# Sheet4.net
KiCad netlist of a schematic drawn in Altium Designer
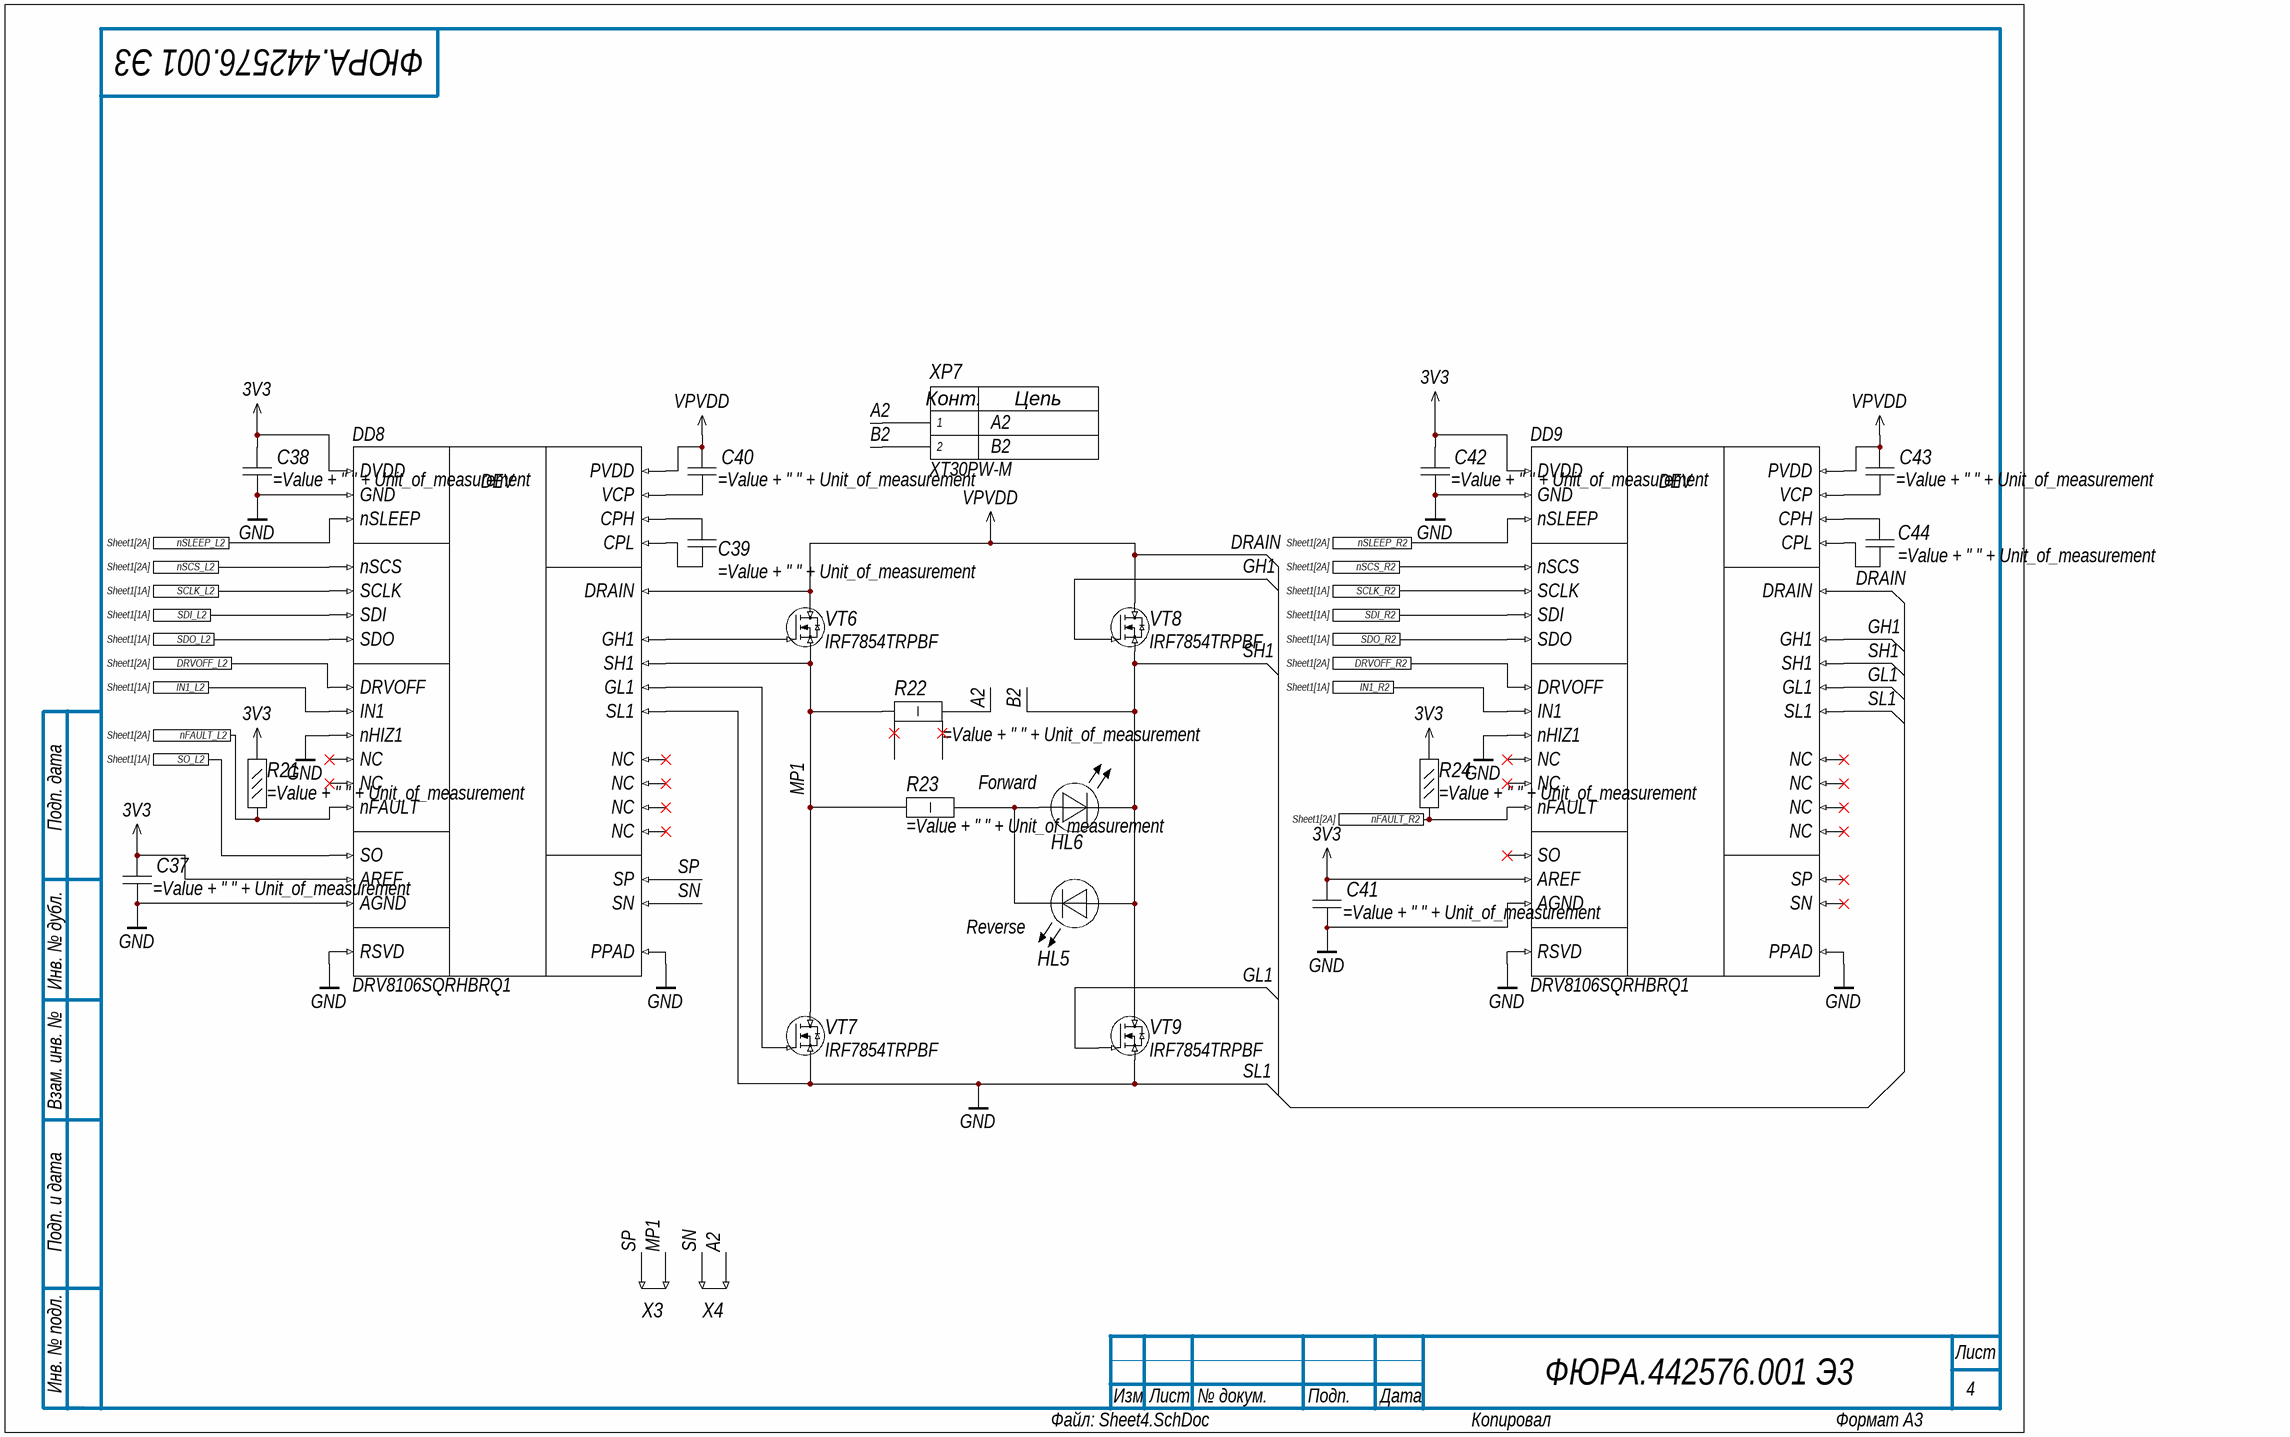
[diagram p0: Sheet4.SchDoc]

(export (version "E")
  (design (tool "Eeschema 10.0.6"))
  (components
    (comp (ref "C37")
      (value "1мкФ 6.3В")
      (footprint "CAP_0603")
      (description "Конденсатор керамический, типоразмера 0603")
      (libsource (lib "SimpleComponents") (part "CAP_0603"))
    )
    (comp (ref "C38")
      (value "1мкФ 6.3В")
      (footprint "CAP_0603")
      (description "Конденсатор керамический, типоразмера 0603")
      (libsource (lib "SimpleComponents") (part "CAP_0603"))
    )
    (comp (ref "C39")
      (value "0,1мкФ 50 В")
      (footprint "CAP_0603")
      (description "Конденсатор керамический, типоразмера 0603")
      (libsource (lib "SimpleComponents") (part "CAP_0603"))
    )
    (comp (ref "C40")
      (value "1мкФ 16 В")
      (footprint "CAP_0603")
      (description "Конденсатор керамический, типоразмера 0603")
      (libsource (lib "SimpleComponents") (part "CAP_0603"))
    )
    (comp (ref "C41")
      (value "1мкФ 6.3В")
      (footprint "CAP_0603")
      (description "Конденсатор керамический, типоразмера 0603")
      (libsource (lib "SimpleComponents") (part "CAP_0603"))
    )
    (comp (ref "C42")
      (value "1мкФ 6.3В")
      (footprint "CAP_0603")
      (description "Конденсатор керамический, типоразмера 0603")
      (libsource (lib "SimpleComponents") (part "CAP_0603"))
    )
    (comp (ref "C43")
      (value "1мкФ 16 В")
      (footprint "CAP_0603")
      (description "Конденсатор керамический, типоразмера 0603")
      (libsource (lib "SimpleComponents") (part "CAP_0603"))
    )
    (comp (ref "C44")
      (value "0,1мкФ 50 В")
      (footprint "CAP_0603")
      (description "Конденсатор керамический, типоразмера 0603")
      (libsource (lib "SimpleComponents") (part "CAP_0603"))
    )
    (comp (ref "DD8")
      (value "DRV8106SQRHBRQ1")
      (footprint "VQFN32")
      (libsource (lib "ICs") (part "DRV8106SQRHBRQ1"))
    )
    (comp (ref "DD9")
      (value "DRV8106SQRHBRQ1")
      (footprint "VQFN32")
      (libsource (lib "ICs") (part "DRV8106SQRHBRQ1"))
    )
    (comp (ref "HL5") (value "3") (footprint "LED_0805") (libsource (lib "Complicated") (part "LED_0805")))
    (comp (ref "HL6") (value "3") (footprint "LED_0805") (libsource (lib "Complicated") (part "LED_0805")))
    (comp (ref "R21")
      (value "10кОм")
      (footprint "RES_0603")
      (description "Резистор, типоразмера 0603")
      (libsource (lib "SimpleComponents") (part "RES_0603"))
    )
    (comp (ref "R22")
      (value "7.5мОм")
      (footprint "RES_2512")
      (description "Резистор, типоразмера 2512")
      (libsource (lib "SimpleComponents") (part "ResShunt_2512"))
    )
    (comp (ref "R23")
      (value "1.8кОм")
      (footprint "RES_2512")
      (description "Резистор, типоразмера 2512")
      (libsource (lib "SimpleComponents") (part "RES_2512"))
    )
    (comp (ref "R24")
      (value "10кОм")
      (footprint "RES_0603")
      (description "Резистор, типоразмера 0603")
      (libsource (lib "SimpleComponents") (part "RES_0603"))
    )
    (comp (ref "VT6")
      (value "IRF7854TRPBF")
      (footprint "SOP-8 WithoutTP")
      (description "Транзистор, HEXFET, N-канал, 80В, 10А [SOIC-8]")
      (libsource (lib "Complicated") (part "IRF7854TRPBF"))
    )
    (comp (ref "VT7")
      (value "IRF7854TRPBF")
      (footprint "SOP-8 WithoutTP")
      (description "Транзистор, HEXFET, N-канал, 80В, 10А [SOIC-8]")
      (libsource (lib "Complicated") (part "IRF7854TRPBF"))
    )
    (comp (ref "VT8")
      (value "IRF7854TRPBF")
      (footprint "SOP-8 WithoutTP")
      (description "Транзистор, HEXFET, N-канал, 80В, 10А [SOIC-8]")
      (libsource (lib "Complicated") (part "IRF7854TRPBF"))
    )
    (comp (ref "VT9")
      (value "IRF7854TRPBF")
      (footprint "SOP-8 WithoutTP")
      (description "Транзистор, HEXFET, N-канал, 80В, 10А [SOIC-8]")
      (libsource (lib "Complicated") (part "IRF7854TRPBF"))
    )
    (comp (ref "X3")
      (value "Обозначение при заказе")
      (footprint "NetTie")
      (description "Описание свойств компонента")
      (libsource (lib "SimpleComponents") (part "NetTie"))
    )
    (comp (ref "X4")
      (value "Обозначение при заказе")
      (footprint "NetTie")
      (description "Описание свойств компонента")
      (libsource (lib "SimpleComponents") (part "NetTie"))
    )
    (comp (ref "XP7")
      (value "XT30PW-M")
      (footprint "XT30PW-M")
      (description "Socket; DC supply; XT30; male; PIN: 2; on PCBs; THT; yellow; 15A; 500V")
      (libsource (lib "SimpleComponents") (part "XT30PW-M"))
    )
  )
  (nets
    (net (code "1") (name "/A2") (class "Default")
      (node (ref "R22") (pin "1") (pinfunction "1_1") (pintype "passive"))
      (node (ref "X4") (pin "2") (pinfunction "2_2") (pintype "input"))
      (node (ref "XP7") (pin "1") (pinfunction "1_1") (pintype "passive"))
    )
    (net (code "2") (name "/B2") (class "Default")
      (node (ref "DD9") (pin "21") (pinfunction "SH1_21") (pintype "input"))
      (node (ref "HL5") (pin "A") (pinfunction "2_A") (pintype "passive"))
      (node (ref "HL6") (pin "C") (pinfunction "1_C") (pintype "passive"))
      (node (ref "VT8") (pin "2") (pinfunction "2_2") (pintype "input"))
      (node (ref "VT9") (pin "3") (pinfunction "3_3") (pintype "input"))
      (node (ref "XP7") (pin "2") (pinfunction "2_2") (pintype "passive"))
    )
    (net (code "3") (name "/DRVOFF_L2") (class "Default")
      (node (ref "DD8") (pin "12") (pinfunction "DRVOFF_12") (pintype "input"))
    )
    (net (code "4") (name "/DRVOFF_R2") (class "Default")
      (node (ref "DD9") (pin "12") (pinfunction "DRVOFF_12") (pintype "input"))
    )
    (net (code "5") (name "/GH1") (class "Default")
      (node (ref "DD9") (pin "20") (pinfunction "GH1_20") (pintype "input"))
      (node (ref "VT8") (pin "1") (pinfunction "1_1") (pintype "input"))
    )
    (net (code "6") (name "/GL1") (class "Default")
      (node (ref "DD9") (pin "22") (pinfunction "GL1_22") (pintype "input"))
      (node (ref "VT9") (pin "1") (pinfunction "1_1") (pintype "input"))
    )
    (net (code "7") (name "/IN1_L2") (class "Default")
      (node (ref "DD8") (pin "7") (pinfunction "IN1_7") (pintype "input"))
    )
    (net (code "8") (name "/IN1_R2") (class "Default")
      (node (ref "DD9") (pin "7") (pinfunction "IN1_7") (pintype "input"))
    )
    (net (code "9") (name "/MP1") (class "Default")
      (node (ref "DD8") (pin "21") (pinfunction "SH1_21") (pintype "input"))
      (node (ref "R22") (pin "2") (pinfunction "2_2") (pintype "passive"))
      (node (ref "R23") (pin "1") (pinfunction "1_1") (pintype "passive"))
      (node (ref "VT6") (pin "2") (pinfunction "2_2") (pintype "input"))
      (node (ref "VT7") (pin "3") (pinfunction "3_3") (pintype "input"))
      (node (ref "X3") (pin "2") (pinfunction "2_2") (pintype "input"))
    )
    (net (code "10") (name "/SCLK_L2") (class "Default")
      (node (ref "DD8") (pin "4") (pinfunction "SCLK_4") (pintype "input"))
    )
    (net (code "11") (name "/SCLK_R2") (class "Default")
      (node (ref "DD9") (pin "4") (pinfunction "SCLK_4") (pintype "input"))
    )
    (net (code "12") (name "/SDI_L2") (class "Default")
      (node (ref "DD8") (pin "5") (pinfunction "SDI_5") (pintype "input"))
    )
    (net (code "13") (name "/SDI_R2") (class "Default")
      (node (ref "DD9") (pin "5") (pinfunction "SDI_5") (pintype "input"))
    )
    (net (code "14") (name "/SDO_L2") (class "Default")
      (node (ref "DD8") (pin "6") (pinfunction "SDO_6") (pintype "input"))
    )
    (net (code "15") (name "/SDO_R2") (class "Default")
      (node (ref "DD9") (pin "6") (pinfunction "SDO_6") (pintype "input"))
    )
    (net (code "16") (name "/SN") (class "Default")
      (node (ref "DD8") (pin "19") (pinfunction "SN_19") (pintype "input"))
      (node (ref "X4") (pin "1") (pinfunction "1_1") (pintype "input"))
    )
    (net (code "17") (name "/SO_L2") (class "Default")
      (node (ref "DD8") (pin "14") (pinfunction "SO_14") (pintype "input"))
    )
    (net (code "18") (name "/SP") (class "Default")
      (node (ref "DD8") (pin "18") (pinfunction "SP_18") (pintype "input"))
      (node (ref "X3") (pin "1") (pinfunction "1_1") (pintype "input"))
    )
    (net (code "19") (name "/nFAULT_L2") (class "Default")
      (node (ref "DD8") (pin "13") (pinfunction "nFAULT_13") (pintype "input"))
      (node (ref "R21") (pin "1") (pinfunction "1_1") (pintype "passive"))
    )
    (net (code "20") (name "/nFAULT_R2") (class "Default")
      (node (ref "DD9") (pin "13") (pinfunction "nFAULT_13") (pintype "input"))
      (node (ref "R24") (pin "1") (pinfunction "1_1") (pintype "passive"))
    )
    (net (code "21") (name "/nSCS_L2") (class "Default")
      (node (ref "DD8") (pin "3") (pinfunction "nSCS_3") (pintype "input"))
    )
    (net (code "22") (name "/nSCS_R2") (class "Default")
      (node (ref "DD9") (pin "3") (pinfunction "nSCS_3") (pintype "input"))
    )
    (net (code "23") (name "/nSLEEP_L2") (class "Default")
      (node (ref "DD8") (pin "11") (pinfunction "nSLEEP_11") (pintype "input"))
    )
    (net (code "24") (name "/nSLEEP_R2") (class "Default")
      (node (ref "DD9") (pin "11") (pinfunction "nSLEEP_11") (pintype "input"))
    )
    (net (code "25") (name "3V3") (class "Default")
      (node (ref "C37") (pin "2") (pintype "passive"))
      (node (ref "C38") (pin "2") (pintype "passive"))
      (node (ref "C41") (pin "2") (pintype "passive"))
      (node (ref "C42") (pin "2") (pintype "passive"))
      (node (ref "DD8") (pin "16") (pinfunction "AREF_16") (pintype "input"))
      (node (ref "DD8") (pin "2") (pinfunction "DVDD_2") (pintype "input"))
      (node (ref "DD9") (pin "16") (pinfunction "AREF_16") (pintype "input"))
      (node (ref "DD9") (pin "2") (pinfunction "DVDD_2") (pintype "input"))
      (node (ref "R21") (pin "2") (pinfunction "2_2") (pintype "passive"))
      (node (ref "R24") (pin "2") (pinfunction "2_2") (pintype "passive"))
    )
    (net (code "26") (name "GND") (class "Default")
      (node (ref "C37") (pin "1") (pintype "passive"))
      (node (ref "C38") (pin "1") (pintype "passive"))
      (node (ref "C41") (pin "1") (pintype "passive"))
      (node (ref "C42") (pin "1") (pintype "passive"))
      (node (ref "DD8") (pin "0") (pinfunction "PPAD_0") (pintype "input"))
      (node (ref "DD8") (pin "1") (pinfunction "GND_1") (pintype "input"))
      (node (ref "DD8") (pin "15") (pinfunction "RSVD_15") (pintype "input"))
      (node (ref "DD8") (pin "17") (pinfunction "AGND_17") (pintype "input"))
      (node (ref "DD8") (pin "23") (pinfunction "SL1_23") (pintype "input"))
      (node (ref "DD8") (pin "8") (pinfunction "nHIZ1_8") (pintype "input"))
      (node (ref "DD9") (pin "0") (pinfunction "PPAD_0") (pintype "input"))
      (node (ref "DD9") (pin "1") (pinfunction "GND_1") (pintype "input"))
      (node (ref "DD9") (pin "15") (pinfunction "RSVD_15") (pintype "input"))
      (node (ref "DD9") (pin "17") (pinfunction "AGND_17") (pintype "input"))
      (node (ref "DD9") (pin "23") (pinfunction "SL1_23") (pintype "input"))
      (node (ref "DD9") (pin "8") (pinfunction "nHIZ1_8") (pintype "input"))
      (node (ref "VT7") (pin "2") (pinfunction "2_2") (pintype "input"))
      (node (ref "VT9") (pin "2") (pinfunction "2_2") (pintype "input"))
    )
    (net (code "27") (name "Net-(DD8-CPH)") (class "Default")
      (node (ref "C39") (pin "2") (pintype "passive"))
      (node (ref "DD8") (pin "31") (pinfunction "CPH_31") (pintype "input"))
    )
    (net (code "28") (name "Net-(DD8-CPL)") (class "Default")
      (node (ref "C39") (pin "1") (pintype "passive"))
      (node (ref "DD8") (pin "32") (pinfunction "CPL_32") (pintype "input"))
    )
    (net (code "29") (name "Net-(DD8-GH1)") (class "Default")
      (node (ref "DD8") (pin "20") (pinfunction "GH1_20") (pintype "input"))
      (node (ref "VT6") (pin "1") (pinfunction "1_1") (pintype "input"))
    )
    (net (code "30") (name "Net-(DD8-GL1)") (class "Default")
      (node (ref "DD8") (pin "22") (pinfunction "GL1_22") (pintype "input"))
      (node (ref "VT7") (pin "1") (pinfunction "1_1") (pintype "input"))
    )
    (net (code "31") (name "Net-(DD8-VCP)") (class "Default")
      (node (ref "C40") (pin "1") (pintype "passive"))
      (node (ref "DD8") (pin "30") (pinfunction "VCP_30") (pintype "input"))
    )
    (net (code "32") (name "Net-(DD9-CPH)") (class "Default")
      (node (ref "C44") (pin "2") (pintype "passive"))
      (node (ref "DD9") (pin "31") (pinfunction "CPH_31") (pintype "input"))
    )
    (net (code "33") (name "Net-(DD9-CPL)") (class "Default")
      (node (ref "C44") (pin "1") (pintype "passive"))
      (node (ref "DD9") (pin "32") (pinfunction "CPL_32") (pintype "input"))
    )
    (net (code "34") (name "Net-(DD9-VCP)") (class "Default")
      (node (ref "C43") (pin "1") (pintype "passive"))
      (node (ref "DD9") (pin "30") (pinfunction "VCP_30") (pintype "input"))
    )
    (net (code "35") (name "Net-(HL5-1)") (class "Default")
      (node (ref "HL5") (pin "C") (pinfunction "1_C") (pintype "passive"))
      (node (ref "HL6") (pin "A") (pinfunction "2_A") (pintype "passive"))
      (node (ref "R23") (pin "2") (pinfunction "2_2") (pintype "passive"))
    )
    (net (code "36") (name "VPVDD") (class "Default")
      (node (ref "C40") (pin "2") (pintype "passive"))
      (node (ref "C43") (pin "2") (pintype "passive"))
      (node (ref "DD8") (pin "28") (pinfunction "DRAIN_28") (pintype "input"))
      (node (ref "DD8") (pin "29") (pinfunction "PVDD_29") (pintype "input"))
      (node (ref "DD9") (pin "28") (pinfunction "DRAIN_28") (pintype "input"))
      (node (ref "DD9") (pin "29") (pinfunction "PVDD_29") (pintype "input"))
      (node (ref "VT6") (pin "3") (pinfunction "3_3") (pintype "input"))
      (node (ref "VT8") (pin "3") (pinfunction "3_3") (pintype "input"))
    )
    (net (code "37") (name "unconnected-(DD8-NC-Pad9)") (class "Default")
      (node (ref "DD8") (pin "9") (pinfunction "NC_9") (pintype "input+no_connect"))
    )
    (net (code "38") (name "unconnected-(DD8-NC-Pad10)") (class "Default")
      (node (ref "DD8") (pin "10") (pinfunction "NC_10") (pintype "input+no_connect"))
    )
    (net (code "39") (name "unconnected-(DD8-NC-Pad24)") (class "Default")
      (node (ref "DD8") (pin "24") (pinfunction "NC_24") (pintype "input+no_connect"))
    )
    (net (code "40") (name "unconnected-(DD8-NC-Pad25)") (class "Default")
      (node (ref "DD8") (pin "25") (pinfunction "NC_25") (pintype "input+no_connect"))
    )
    (net (code "41") (name "unconnected-(DD8-NC-Pad26)") (class "Default")
      (node (ref "DD8") (pin "26") (pinfunction "NC_26") (pintype "input+no_connect"))
    )
    (net (code "42") (name "unconnected-(DD8-NC-Pad27)") (class "Default")
      (node (ref "DD8") (pin "27") (pinfunction "NC_27") (pintype "input+no_connect"))
    )
    (net (code "43") (name "unconnected-(DD9-NC-Pad9)") (class "Default")
      (node (ref "DD9") (pin "9") (pinfunction "NC_9") (pintype "input+no_connect"))
    )
    (net (code "44") (name "unconnected-(DD9-NC-Pad10)") (class "Default")
      (node (ref "DD9") (pin "10") (pinfunction "NC_10") (pintype "input+no_connect"))
    )
    (net (code "45") (name "unconnected-(DD9-NC-Pad24)") (class "Default")
      (node (ref "DD9") (pin "24") (pinfunction "NC_24") (pintype "input+no_connect"))
    )
    (net (code "46") (name "unconnected-(DD9-NC-Pad25)") (class "Default")
      (node (ref "DD9") (pin "25") (pinfunction "NC_25") (pintype "input+no_connect"))
    )
    (net (code "47") (name "unconnected-(DD9-NC-Pad26)") (class "Default")
      (node (ref "DD9") (pin "26") (pinfunction "NC_26") (pintype "input+no_connect"))
    )
    (net (code "48") (name "unconnected-(DD9-NC-Pad27)") (class "Default")
      (node (ref "DD9") (pin "27") (pinfunction "NC_27") (pintype "input+no_connect"))
    )
    (net (code "49") (name "unconnected-(DD9-SN-Pad19)") (class "Default")
      (node (ref "DD9") (pin "19") (pinfunction "SN_19") (pintype "input+no_connect"))
    )
    (net (code "50") (name "unconnected-(DD9-SO-Pad14)") (class "Default")
      (node (ref "DD9") (pin "14") (pinfunction "SO_14") (pintype "input+no_connect"))
    )
    (net (code "51") (name "unconnected-(DD9-SP-Pad18)") (class "Default")
      (node (ref "DD9") (pin "18") (pinfunction "SP_18") (pintype "input+no_connect"))
    )
    (net (code "52") (name "unconnected-(R22-Pad1)") (class "Default")
      (node (ref "R22") (pin "1") (pinfunction "1_1") (pintype "passive+no_connect"))
    )
    (net (code "53") (name "unconnected-(R22-Pad2)") (class "Default")
      (node (ref "R22") (pin "2") (pinfunction "2_2") (pintype "passive+no_connect"))
    )
  )
)
